# ripples_v90.net
KiCad netlist of a schematic drawn in EAGLE
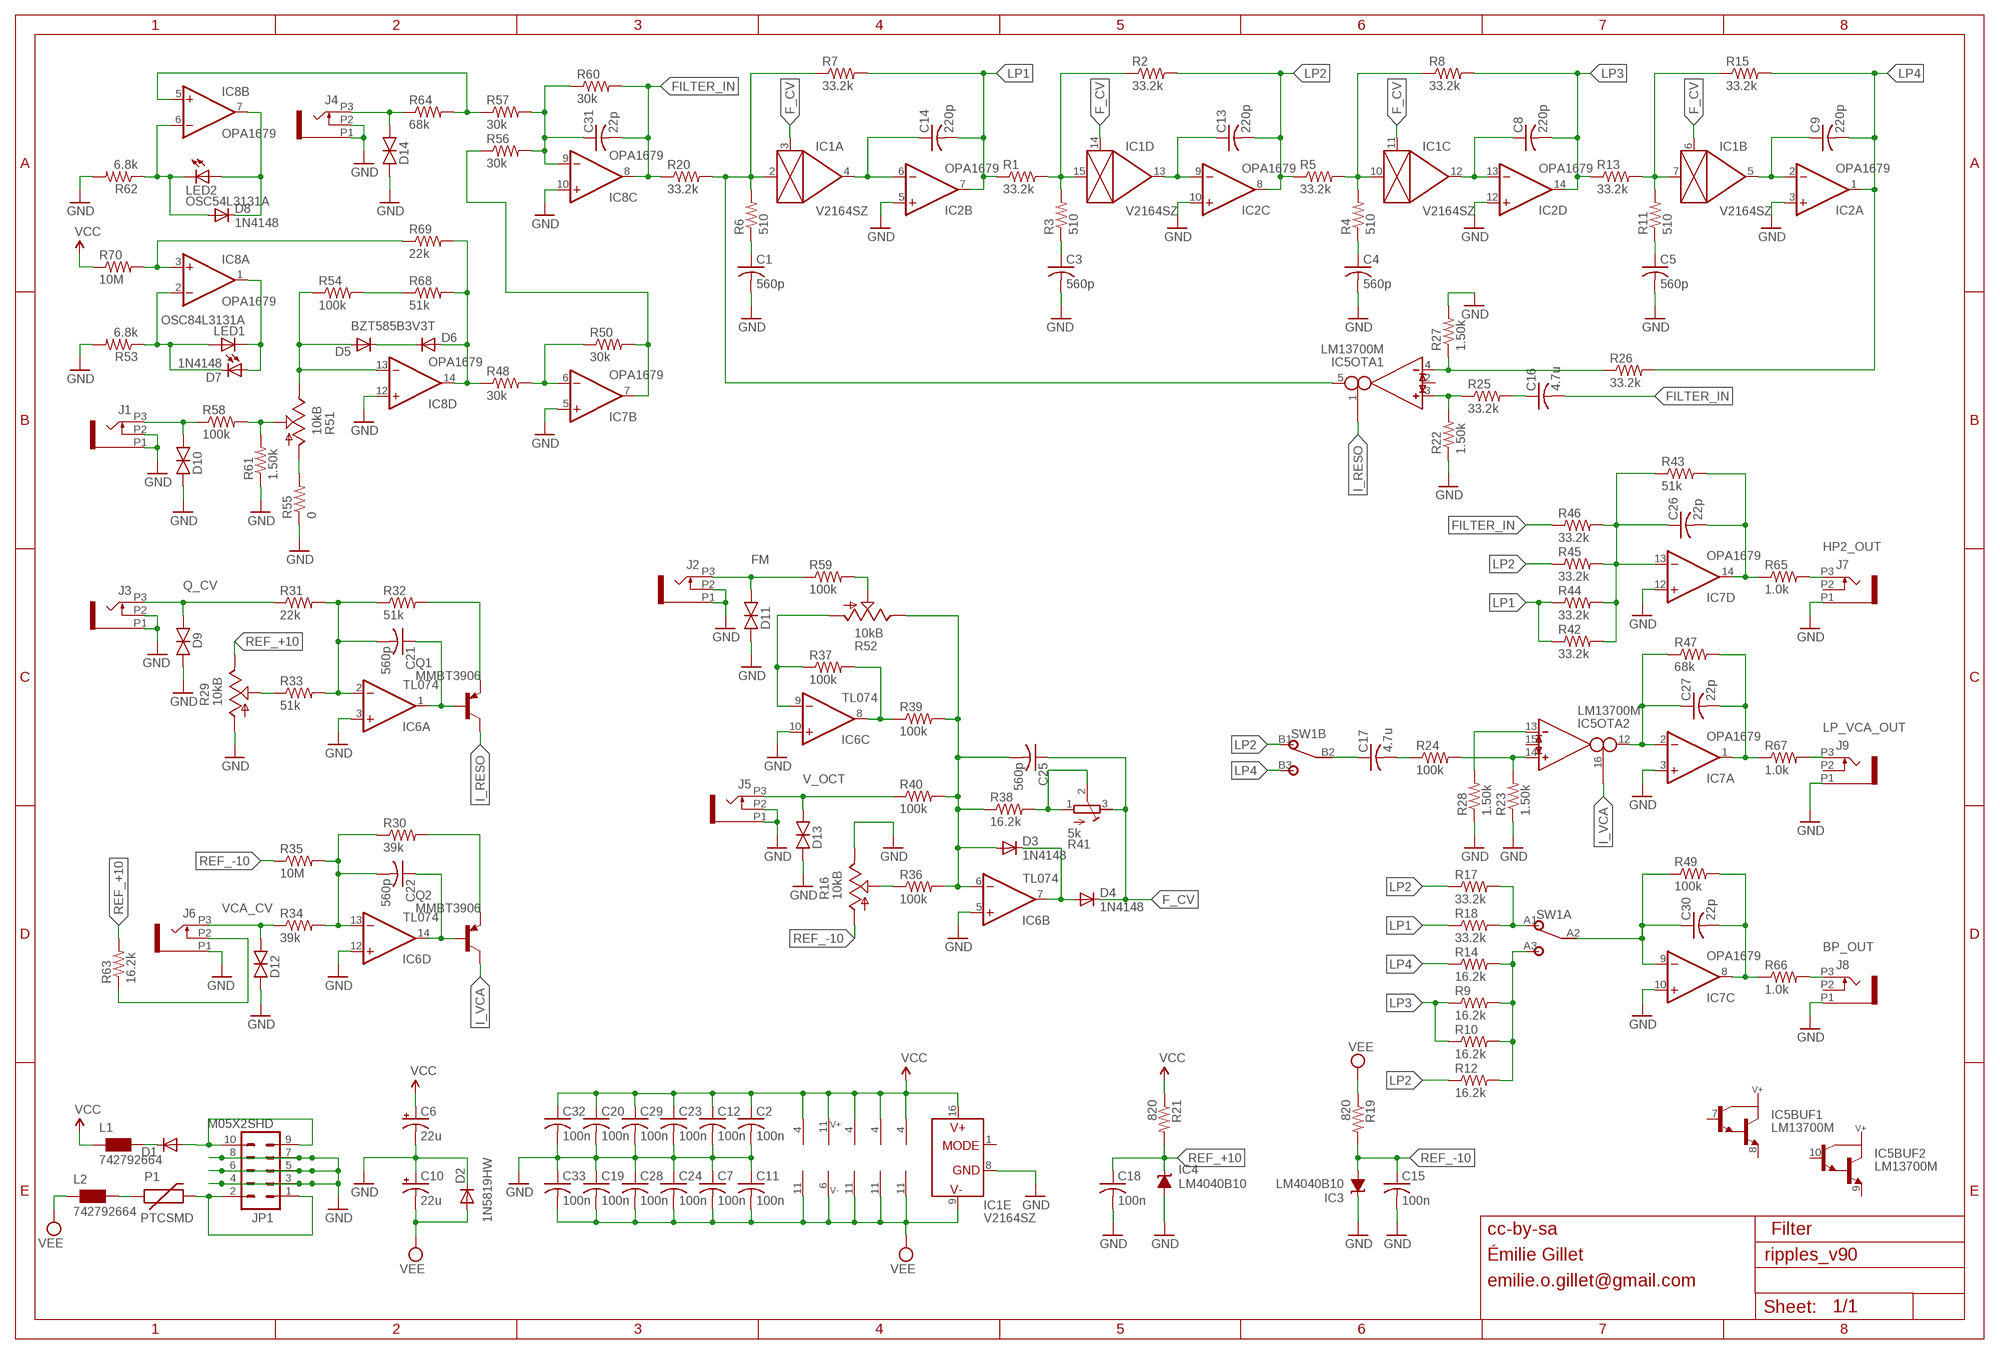
[diagram p0: schematic, sheet 1]

(export (version "E")
  (design (tool "Eeschema 10.0.6"))
  (components
    (comp (ref "C1")
      (value "560p")
      (footprint "eagle-import:C0402")
      (libsource (lib "eagle-import") (part "C-USC0402"))
    )
    (comp (ref "C2")
      (value "100n")
      (footprint "eagle-import:C0402")
      (libsource (lib "eagle-import") (part "C-USC0402"))
    )
    (comp (ref "C3")
      (value "560p")
      (footprint "eagle-import:C0402")
      (libsource (lib "eagle-import") (part "C-USC0402"))
    )
    (comp (ref "C4")
      (value "560p")
      (footprint "eagle-import:C0402")
      (libsource (lib "eagle-import") (part "C-USC0402"))
    )
    (comp (ref "C5")
      (value "560p")
      (footprint "eagle-import:C0402")
      (libsource (lib "eagle-import") (part "C-USC0402"))
    )
    (comp (ref "C6")
      (value "22u")
      (footprint "eagle-import:PANASONIC_B")
      (libsource (lib "eagle-import") (part "CPOL-USB"))
    )
    (comp (ref "C7")
      (value "100n")
      (footprint "eagle-import:C0402")
      (libsource (lib "eagle-import") (part "C-USC0402"))
    )
    (comp (ref "C8")
      (value "220p")
      (footprint "eagle-import:C0603")
      (libsource (lib "eagle-import") (part "C-USC0603"))
    )
    (comp (ref "C9")
      (value "220p")
      (footprint "eagle-import:C0603")
      (libsource (lib "eagle-import") (part "C-USC0603"))
    )
    (comp (ref "C10")
      (value "22u")
      (footprint "eagle-import:PANASONIC_B")
      (libsource (lib "eagle-import") (part "CPOL-USB"))
    )
    (comp (ref "C11")
      (value "100n")
      (footprint "eagle-import:C0402")
      (libsource (lib "eagle-import") (part "C-USC0402"))
    )
    (comp (ref "C12")
      (value "100n")
      (footprint "eagle-import:C0402")
      (libsource (lib "eagle-import") (part "C-USC0402"))
    )
    (comp (ref "C13")
      (value "220p")
      (footprint "eagle-import:C0603")
      (libsource (lib "eagle-import") (part "C-USC0603"))
    )
    (comp (ref "C14")
      (value "220p")
      (footprint "eagle-import:C0603")
      (libsource (lib "eagle-import") (part "C-USC0603"))
    )
    (comp (ref "C15")
      (value "100n")
      (footprint "eagle-import:C0402")
      (libsource (lib "eagle-import") (part "C-USC0402"))
    )
    (comp (ref "C16")
      (value "4.7u")
      (footprint "eagle-import:C1206")
      (libsource (lib "eagle-import") (part "C-USC1206"))
    )
    (comp (ref "C17")
      (value "4.7u")
      (footprint "eagle-import:C1206")
      (libsource (lib "eagle-import") (part "C-USC1206"))
    )
    (comp (ref "C18")
      (value "100n")
      (footprint "eagle-import:C0402")
      (libsource (lib "eagle-import") (part "C-USC0402"))
    )
    (comp (ref "C19")
      (value "100n")
      (footprint "eagle-import:C0402")
      (libsource (lib "eagle-import") (part "C-USC0402"))
    )
    (comp (ref "C20")
      (value "100n")
      (footprint "eagle-import:C0402")
      (libsource (lib "eagle-import") (part "C-USC0402"))
    )
    (comp (ref "C21")
      (value "560p")
      (footprint "eagle-import:C0402")
      (libsource (lib "eagle-import") (part "C-USC0402"))
    )
    (comp (ref "C22")
      (value "560p")
      (footprint "eagle-import:C0402")
      (libsource (lib "eagle-import") (part "C-USC0402"))
    )
    (comp (ref "C23")
      (value "100n")
      (footprint "eagle-import:C0402")
      (libsource (lib "eagle-import") (part "C-USC0402"))
    )
    (comp (ref "C24")
      (value "100n")
      (footprint "eagle-import:C0402")
      (libsource (lib "eagle-import") (part "C-USC0402"))
    )
    (comp (ref "C25")
      (value "560p")
      (footprint "eagle-import:C0402")
      (libsource (lib "eagle-import") (part "C-USC0402"))
    )
    (comp (ref "C26")
      (value "22p")
      (footprint "eagle-import:C0402")
      (libsource (lib "eagle-import") (part "C-USC0402"))
    )
    (comp (ref "C27")
      (value "22p")
      (footprint "eagle-import:C0402")
      (libsource (lib "eagle-import") (part "C-USC0402"))
    )
    (comp (ref "C28")
      (value "100n")
      (footprint "eagle-import:C0402")
      (libsource (lib "eagle-import") (part "C-USC0402"))
    )
    (comp (ref "C29")
      (value "100n")
      (footprint "eagle-import:C0402")
      (libsource (lib "eagle-import") (part "C-USC0402"))
    )
    (comp (ref "C30")
      (value "22p")
      (footprint "eagle-import:C0402")
      (libsource (lib "eagle-import") (part "C-USC0402"))
    )
    (comp (ref "C31")
      (value "22p")
      (footprint "eagle-import:C0402")
      (libsource (lib "eagle-import") (part "C-USC0402"))
    )
    (comp (ref "C32")
      (value "100n")
      (footprint "eagle-import:C0402")
      (libsource (lib "eagle-import") (part "C-USC0402"))
    )
    (comp (ref "C33")
      (value "100n")
      (footprint "eagle-import:C0402")
      (libsource (lib "eagle-import") (part "C-USC0402"))
    )
    (comp (ref "D1")
      (value "1N5819HW")
      (footprint "eagle-import:SOD123")
      (libsource (lib "eagle-import") (part "DIODE-SOD123"))
    )
    (comp (ref "D2")
      (value "1N5819HW")
      (footprint "eagle-import:SOD123")
      (libsource (lib "eagle-import") (part "DIODE-SOD123"))
    )
    (comp (ref "D3")
      (value "1N4148")
      (footprint "eagle-import:SOD523")
      (libsource (lib "eagle-import") (part "DIODE-SOD523"))
    )
    (comp (ref "D4")
      (value "1N4148")
      (footprint "eagle-import:SOD523")
      (libsource (lib "eagle-import") (part "DIODE-SOD523"))
    )
    (comp (ref "D5")
      (value "BZT585B3V3T")
      (footprint "eagle-import:SOD523")
      (libsource (lib "eagle-import") (part "DIODE-SOD523"))
    )
    (comp (ref "D6")
      (value "BZT585B3V3T")
      (footprint "eagle-import:SOD523")
      (libsource (lib "eagle-import") (part "DIODE-SOD523"))
    )
    (comp (ref "D7")
      (value "1N4148")
      (footprint "eagle-import:SOD523")
      (libsource (lib "eagle-import") (part "DIODE-SOD523"))
    )
    (comp (ref "D8")
      (value "1N4148")
      (footprint "eagle-import:SOD523")
      (libsource (lib "eagle-import") (part "DIODE-SOD523"))
    )
    (comp (ref "D9")
      (value "TVS")
      (footprint "eagle-import:0603")
      (libsource (lib "eagle-import") (part "TVS"))
    )
    (comp (ref "D10")
      (value "TVS")
      (footprint "eagle-import:0603")
      (libsource (lib "eagle-import") (part "TVS"))
    )
    (comp (ref "D11")
      (value "TVS")
      (footprint "eagle-import:0603")
      (libsource (lib "eagle-import") (part "TVS"))
    )
    (comp (ref "D12")
      (value "TVS")
      (footprint "eagle-import:0603")
      (libsource (lib "eagle-import") (part "TVS"))
    )
    (comp (ref "D13")
      (value "TVS")
      (footprint "eagle-import:0603")
      (libsource (lib "eagle-import") (part "TVS"))
    )
    (comp (ref "D14")
      (value "TVS")
      (footprint "eagle-import:0603")
      (libsource (lib "eagle-import") (part "TVS"))
    )
    (comp (ref "IC1")
      (value "V2164SZ")
      (footprint "eagle-import:SOIC16N")
      (libsource (lib "eagle-import") (part "SSM2164S"))
    )
    (comp (ref "IC2")
      (value "OPA1679")
      (footprint "eagle-import:TSSOP14_065")
      (libsource (lib "eagle-import") (part "OPA1679PW"))
    )
    (comp (ref "IC3")
      (value "LM4040B10")
      (footprint "eagle-import:DBZ_R-PDSO-G3")
      (libsource (lib "eagle-import") (part "LM4041DBZB12"))
    )
    (comp (ref "IC4")
      (value "LM4040B10")
      (footprint "eagle-import:DBZ_R-PDSO-G3")
      (libsource (lib "eagle-import") (part "LM4041DBZB12"))
    )
    (comp (ref "IC5")
      (value "LM13700M")
      (footprint "eagle-import:SO16")
      (libsource (lib "eagle-import") (part "LM13700M"))
    )
    (comp (ref "IC6")
      (value "TL074")
      (footprint "eagle-import:TSSOP14_065")
      (libsource (lib "eagle-import") (part "TL074PW"))
    )
    (comp (ref "IC7")
      (value "OPA1679")
      (footprint "eagle-import:TSSOP14_065")
      (libsource (lib "eagle-import") (part "OPA1679PW"))
    )
    (comp (ref "IC8")
      (value "OPA1679")
      (footprint "eagle-import:TSSOP14_065")
      (libsource (lib "eagle-import") (part "OPA1679PW"))
    )
    (comp (ref "J1")
      (value "PJ301_THONKICONNTME")
      (footprint "eagle-import:WQP_PJ_301M_TME")
      (libsource (lib "eagle-import") (part "PJ301_THONKICONNTME"))
    )
    (comp (ref "J2")
      (value "PJ301_THONKICONNTME")
      (footprint "eagle-import:WQP_PJ_301M_TME")
      (libsource (lib "eagle-import") (part "PJ301_THONKICONNTME"))
    )
    (comp (ref "J3")
      (value "PJ301_THONKICONNTME")
      (footprint "eagle-import:WQP_PJ_301M_TME")
      (libsource (lib "eagle-import") (part "PJ301_THONKICONNTME"))
    )
    (comp (ref "J4")
      (value "PJ301_THONKICONNTME")
      (footprint "eagle-import:WQP_PJ_301M_TME")
      (libsource (lib "eagle-import") (part "PJ301_THONKICONNTME"))
    )
    (comp (ref "J5")
      (value "PJ301_THONKICONNTME")
      (footprint "eagle-import:WQP_PJ_301M_TME")
      (libsource (lib "eagle-import") (part "PJ301_THONKICONNTME"))
    )
    (comp (ref "J6")
      (value "PJ301_THONKICONNTME")
      (footprint "eagle-import:WQP_PJ_301M_TME")
      (libsource (lib "eagle-import") (part "PJ301_THONKICONNTME"))
    )
    (comp (ref "J7")
      (value "PJ301_THONKICONNTME")
      (footprint "eagle-import:WQP_PJ_301M_TME")
      (libsource (lib "eagle-import") (part "PJ301_THONKICONNTME"))
    )
    (comp (ref "J8")
      (value "PJ301_THONKICONNTME")
      (footprint "eagle-import:WQP_PJ_301M_TME")
      (libsource (lib "eagle-import") (part "PJ301_THONKICONNTME"))
    )
    (comp (ref "J9")
      (value "PJ301_THONKICONNTME")
      (footprint "eagle-import:WQP_PJ_301M_TME")
      (libsource (lib "eagle-import") (part "PJ301_THONKICONNTME"))
    )
    (comp (ref "JP1")
      (value "M05X2SHD")
      (footprint "eagle-import:2X5-SHROUDED")
      (libsource (lib "eagle-import") (part "M05X2SHD"))
    )
    (comp (ref "L1")
      (value "742792664")
      (footprint "eagle-import:0603")
      (libsource (lib "eagle-import") (part "WE-CBF_0603"))
    )
    (comp (ref "L2")
      (value "742792664")
      (footprint "eagle-import:0603")
      (libsource (lib "eagle-import") (part "WE-CBF_0603"))
    )
    (comp (ref "LED1")
      (value "OSC84L3131A")
      (footprint "eagle-import:LED3MM")
      (libsource (lib "eagle-import") (part "LED3MM"))
    )
    (comp (ref "LED2")
      (value "OSC54L3131A")
      (footprint "eagle-import:LED3MM")
      (libsource (lib "eagle-import") (part "LED3MM"))
    )
    (comp (ref "P1")
      (value "PTCSMD")
      (footprint "eagle-import:PTC-1206")
      (libsource (lib "eagle-import") (part "PTCSMD"))
    )
    (comp (ref "Q1")
      (value "MMBT3906")
      (footprint "eagle-import:SOT23-BEC")
      (libsource (lib "eagle-import") (part "-PNP-SOT23-BECMMBT3906LT1"))
    )
    (comp (ref "Q2")
      (value "MMBT3906")
      (footprint "eagle-import:SOT23-BEC")
      (libsource (lib "eagle-import") (part "-PNP-SOT23-BECMMBT3906LT1"))
    )
    (comp (ref "R1")
      (value "33.2k")
      (footprint "eagle-import:R0402")
      (libsource (lib "eagle-import") (part "R-US_R0402"))
    )
    (comp (ref "R2")
      (value "33.2k")
      (footprint "eagle-import:R0402")
      (libsource (lib "eagle-import") (part "R-US_R0402"))
    )
    (comp (ref "R3")
      (value "510")
      (footprint "eagle-import:R0402")
      (libsource (lib "eagle-import") (part "R-US_R0402"))
    )
    (comp (ref "R4")
      (value "510")
      (footprint "eagle-import:R0402")
      (libsource (lib "eagle-import") (part "R-US_R0402"))
    )
    (comp (ref "R5")
      (value "33.2k")
      (footprint "eagle-import:R0402")
      (libsource (lib "eagle-import") (part "R-US_R0402"))
    )
    (comp (ref "R6")
      (value "510")
      (footprint "eagle-import:R0402")
      (libsource (lib "eagle-import") (part "R-US_R0402"))
    )
    (comp (ref "R7")
      (value "33.2k")
      (footprint "eagle-import:R0402")
      (libsource (lib "eagle-import") (part "R-US_R0402"))
    )
    (comp (ref "R8")
      (value "33.2k")
      (footprint "eagle-import:R0402")
      (libsource (lib "eagle-import") (part "R-US_R0402"))
    )
    (comp (ref "R9")
      (value "16.2k")
      (footprint "eagle-import:R0402")
      (libsource (lib "eagle-import") (part "R-US_R0402"))
    )
    (comp (ref "R10")
      (value "16.2k")
      (footprint "eagle-import:R0402")
      (libsource (lib "eagle-import") (part "R-US_R0402"))
    )
    (comp (ref "R11")
      (value "510")
      (footprint "eagle-import:R0402")
      (libsource (lib "eagle-import") (part "R-US_R0402"))
    )
    (comp (ref "R12")
      (value "16.2k")
      (footprint "eagle-import:R0402")
      (libsource (lib "eagle-import") (part "R-US_R0402"))
    )
    (comp (ref "R13")
      (value "33.2k")
      (footprint "eagle-import:R0402")
      (libsource (lib "eagle-import") (part "R-US_R0402"))
    )
    (comp (ref "R14")
      (value "16.2k")
      (footprint "eagle-import:R0402")
      (libsource (lib "eagle-import") (part "R-US_R0402"))
    )
    (comp (ref "R15")
      (value "33.2k")
      (footprint "eagle-import:R0402")
      (libsource (lib "eagle-import") (part "R-US_R0402"))
    )
    (comp (ref "R16")
      (value "10kB")
      (footprint "eagle-import:ALPS_POT_VERTICAL_PS")
      (libsource (lib "eagle-import") (part "POT_USVERTICAL_PS"))
    )
    (comp (ref "R17")
      (value "33.2k")
      (footprint "eagle-import:R0402")
      (libsource (lib "eagle-import") (part "R-US_R0402"))
    )
    (comp (ref "R18")
      (value "33.2k")
      (footprint "eagle-import:R0402")
      (libsource (lib "eagle-import") (part "R-US_R0402"))
    )
    (comp (ref "R19")
      (value "820")
      (footprint "eagle-import:R0402")
      (libsource (lib "eagle-import") (part "resistor_R-US_R0402"))
    )
    (comp (ref "R20")
      (value "33.2k")
      (footprint "eagle-import:R0402")
      (libsource (lib "eagle-import") (part "R-US_R0402"))
    )
    (comp (ref "R21")
      (value "820")
      (footprint "eagle-import:R0402")
      (libsource (lib "eagle-import") (part "R-US_R0402"))
    )
    (comp (ref "R22")
      (value "1.50k")
      (footprint "eagle-import:R0402")
      (libsource (lib "eagle-import") (part "R-US_R0402"))
    )
    (comp (ref "R23")
      (value "1.50k")
      (footprint "eagle-import:R0402")
      (libsource (lib "eagle-import") (part "R-US_R0402"))
    )
    (comp (ref "R24")
      (value "100k")
      (footprint "eagle-import:R0402")
      (libsource (lib "eagle-import") (part "R-US_R0402"))
    )
    (comp (ref "R25")
      (value "33.2k")
      (footprint "eagle-import:R0402")
      (libsource (lib "eagle-import") (part "R-US_R0402"))
    )
    (comp (ref "R26")
      (value "33.2k")
      (footprint "eagle-import:R0402")
      (libsource (lib "eagle-import") (part "R-US_R0402"))
    )
    (comp (ref "R27")
      (value "1.50k")
      (footprint "eagle-import:R0402")
      (libsource (lib "eagle-import") (part "R-US_R0402"))
    )
    (comp (ref "R28")
      (value "1.50k")
      (footprint "eagle-import:R0402")
      (libsource (lib "eagle-import") (part "R-US_R0402"))
    )
    (comp (ref "R29")
      (value "10kB")
      (footprint "eagle-import:ALPS_POT_VERTICAL_PS")
      (libsource (lib "eagle-import") (part "POT_USVERTICAL_PS"))
    )
    (comp (ref "R30")
      (value "39k")
      (footprint "eagle-import:R0402")
      (libsource (lib "eagle-import") (part "R-US_R0402"))
    )
    (comp (ref "R31")
      (value "22k")
      (footprint "eagle-import:R0402")
      (libsource (lib "eagle-import") (part "R-US_R0402"))
    )
    (comp (ref "R32")
      (value "51k")
      (footprint "eagle-import:R0402")
      (libsource (lib "eagle-import") (part "R-US_R0402"))
    )
    (comp (ref "R33")
      (value "51k")
      (footprint "eagle-import:R0402")
      (libsource (lib "eagle-import") (part "R-US_R0402"))
    )
    (comp (ref "R34")
      (value "39k")
      (footprint "eagle-import:R0402")
      (libsource (lib "eagle-import") (part "R-US_R0402"))
    )
    (comp (ref "R35")
      (value "10M")
      (footprint "eagle-import:R0402")
      (libsource (lib "eagle-import") (part "R-US_R0402"))
    )
    (comp (ref "R36")
      (value "100k")
      (footprint "eagle-import:R0402")
      (libsource (lib "eagle-import") (part "R-US_R0402"))
    )
    (comp (ref "R37")
      (value "100k")
      (footprint "eagle-import:R0402")
      (libsource (lib "eagle-import") (part "R-US_R0402"))
    )
    (comp (ref "R38")
      (value "16.2k")
      (footprint "eagle-import:R0402")
      (libsource (lib "eagle-import") (part "R-US_R0402"))
    )
    (comp (ref "R39")
      (value "100k")
      (footprint "eagle-import:R0402")
      (libsource (lib "eagle-import") (part "R-US_R0402"))
    )
    (comp (ref "R40")
      (value "100k")
      (footprint "eagle-import:R0402")
      (libsource (lib "eagle-import") (part "R-US_R0402"))
    )
    (comp (ref "R41")
      (value "5k")
      (footprint "eagle-import:RTRIM3296X")
      (libsource (lib "eagle-import") (part "R-TRIMM3296X"))
    )
    (comp (ref "R42")
      (value "33.2k")
      (footprint "eagle-import:R0402")
      (libsource (lib "eagle-import") (part "R-US_R0402"))
    )
    (comp (ref "R43")
      (value "51k")
      (footprint "eagle-import:R0402")
      (libsource (lib "eagle-import") (part "R-US_R0402"))
    )
    (comp (ref "R44")
      (value "33.2k")
      (footprint "eagle-import:R0402")
      (libsource (lib "eagle-import") (part "R-US_R0402"))
    )
    (comp (ref "R45")
      (value "33.2k")
      (footprint "eagle-import:R0402")
      (libsource (lib "eagle-import") (part "R-US_R0402"))
    )
    (comp (ref "R46")
      (value "33.2k")
      (footprint "eagle-import:R0402")
      (libsource (lib "eagle-import") (part "R-US_R0402"))
    )
    (comp (ref "R47")
      (value "68k")
      (footprint "eagle-import:R0402")
      (libsource (lib "eagle-import") (part "R-US_R0402"))
    )
    (comp (ref "R48")
      (value "30k")
      (footprint "eagle-import:R0402")
      (libsource (lib "eagle-import") (part "R-US_R0402"))
    )
    (comp (ref "R49")
      (value "100k")
      (footprint "eagle-import:R0402")
      (libsource (lib "eagle-import") (part "R-US_R0402"))
    )
    (comp (ref "R50")
      (value "30k")
      (footprint "eagle-import:R0402")
      (libsource (lib "eagle-import") (part "R-US_R0402"))
    )
    (comp (ref "R51")
      (value "10kB")
      (footprint "eagle-import:ALPS_POT_NARROW")
      (libsource (lib "eagle-import") (part "POT_USVERTICAL_NARROW"))
    )
    (comp (ref "R52")
      (value "10kB")
      (footprint "eagle-import:ALPS_POT_NARROW")
      (libsource (lib "eagle-import") (part "POT_USVERTICAL_NARROW"))
    )
    (comp (ref "R53")
      (value "6.8k")
      (footprint "eagle-import:R0402")
      (libsource (lib "eagle-import") (part "R-US_R0402"))
    )
    (comp (ref "R54")
      (value "100k")
      (footprint "eagle-import:R0402")
      (libsource (lib "eagle-import") (part "R-US_R0402"))
    )
    (comp (ref "R55")
      (value "0")
      (footprint "eagle-import:R0402")
      (libsource (lib "eagle-import") (part "R-US_R0402"))
    )
    (comp (ref "R56")
      (value "30k")
      (footprint "eagle-import:R0402")
      (libsource (lib "eagle-import") (part "R-US_R0402"))
    )
    (comp (ref "R57")
      (value "30k")
      (footprint "eagle-import:R0402")
      (libsource (lib "eagle-import") (part "R-US_R0402"))
    )
    (comp (ref "R58")
      (value "100k")
      (footprint "eagle-import:R0402")
      (libsource (lib "eagle-import") (part "R-US_R0402"))
    )
    (comp (ref "R59")
      (value "100k")
      (footprint "eagle-import:R0402")
      (libsource (lib "eagle-import") (part "R-US_R0402"))
    )
    (comp (ref "R60")
      (value "30k")
      (footprint "eagle-import:R0402")
      (libsource (lib "eagle-import") (part "R-US_R0402"))
    )
    (comp (ref "R61")
      (value "1.50k")
      (footprint "eagle-import:R0402")
      (libsource (lib "eagle-import") (part "R-US_R0402"))
    )
    (comp (ref "R62")
      (value "6.8k")
      (footprint "eagle-import:R0402")
      (libsource (lib "eagle-import") (part "R-US_R0402"))
    )
    (comp (ref "R63")
      (value "16.2k")
      (footprint "eagle-import:R0402")
      (libsource (lib "eagle-import") (part "R-US_R0402"))
    )
    (comp (ref "R64")
      (value "68k")
      (footprint "eagle-import:R0402")
      (libsource (lib "eagle-import") (part "R-US_R0402"))
    )
    (comp (ref "R65")
      (value "1.0k")
      (footprint "eagle-import:R0603")
      (libsource (lib "eagle-import") (part "R-US_R0603"))
    )
    (comp (ref "R66")
      (value "1.0k")
      (footprint "eagle-import:R0603")
      (libsource (lib "eagle-import") (part "R-US_R0603"))
    )
    (comp (ref "R67")
      (value "1.0k")
      (footprint "eagle-import:R0603")
      (libsource (lib "eagle-import") (part "R-US_R0603"))
    )
    (comp (ref "R68")
      (value "51k")
      (footprint "eagle-import:R0402")
      (libsource (lib "eagle-import") (part "R-US_R0402"))
    )
    (comp (ref "R69")
      (value "22k")
      (footprint "eagle-import:R0402")
      (libsource (lib "eagle-import") (part "R-US_R0402"))
    )
    (comp (ref "R70")
      (value "10M")
      (footprint "eagle-import:R0402")
      (libsource (lib "eagle-import") (part "R-US_R0402"))
    )
    (comp (ref "SW1")
      (value "S-ON-ON-ONSS70070F-0202")
      (footprint "eagle-import:SS70070F-0202")
      (libsource (lib "eagle-import") (part "S-ON-ON-ONSS70070F-0202"))
    )
  )
  (nets
    (net (code "1") (name "/BP_OUT") (class "Default")
      (node (ref "J8") (pin "P3") (pinfunction "3_P3") (pintype "passive"))
      (node (ref "R66") (pin "2") (pinfunction "2_2") (pintype "passive"))
    )
    (net (code "2") (name "/FM") (class "Default")
      (node (ref "D11") (pin "2") (pinfunction "C_2") (pintype "passive"))
      (node (ref "J2") (pin "P3") (pinfunction "3_P3") (pintype "passive"))
      (node (ref "R59") (pin "1") (pinfunction "1_1") (pintype "passive"))
    )
    (net (code "3") (name "/HP2_OUT") (class "Default")
      (node (ref "J7") (pin "P3") (pinfunction "3_P3") (pintype "passive"))
      (node (ref "R65") (pin "2") (pinfunction "2_2") (pintype "passive"))
    )
    (net (code "4") (name "/LP_VCA_OUT") (class "Default")
      (node (ref "J9") (pin "P3") (pinfunction "3_P3") (pintype "passive"))
      (node (ref "R67") (pin "2") (pinfunction "2_2") (pintype "passive"))
    )
    (net (code "5") (name "/Q_CV") (class "Default")
      (node (ref "D9") (pin "2") (pinfunction "C_2") (pintype "passive"))
      (node (ref "J3") (pin "P3") (pinfunction "3_P3") (pintype "passive"))
      (node (ref "R31") (pin "1") (pinfunction "1_1") (pintype "passive"))
    )
    (net (code "6") (name "/VCA_CV") (class "Default")
      (node (ref "D12") (pin "2") (pinfunction "C_2") (pintype "passive"))
      (node (ref "J6") (pin "P3") (pinfunction "3_P3") (pintype "passive"))
      (node (ref "R34") (pin "1") (pinfunction "1_1") (pintype "passive"))
    )
    (net (code "7") (name "/V_OCT") (class "Default")
      (node (ref "D13") (pin "2") (pinfunction "C_2") (pintype "passive"))
      (node (ref "J5") (pin "P3") (pinfunction "3_P3") (pintype "passive"))
      (node (ref "R40") (pin "1") (pinfunction "1_1") (pintype "passive"))
    )
    (net (code "8") (name "FILTER_IN") (class "Default")
      (node (ref "C16") (pin "2") (pinfunction "2_2") (pintype "passive"))
      (node (ref "C31") (pin "2") (pinfunction "2_2") (pintype "passive"))
      (node (ref "IC8") (pin "8") (pinfunction "OUT_8") (pintype "output"))
      (node (ref "R20") (pin "1") (pinfunction "1_1") (pintype "passive"))
      (node (ref "R46") (pin "1") (pinfunction "1_1") (pintype "passive"))
      (node (ref "R60") (pin "2") (pinfunction "2_2") (pintype "passive"))
    )
    (net (code "9") (name "F_CV") (class "Default")
      (node (ref "C25") (pin "1") (pinfunction "1_1") (pintype "passive"))
      (node (ref "D4") (pin "C") (pinfunction "C_C") (pintype "passive"))
      (node (ref "IC1") (pin "11") (pinfunction "CTRL_11") (pintype "input"))
      (node (ref "IC1") (pin "14") (pinfunction "CTRL_14") (pintype "input"))
      (node (ref "IC1") (pin "3") (pinfunction "CTRL_3") (pintype "input"))
      (node (ref "IC1") (pin "6") (pinfunction "CTRL_6") (pintype "input"))
      (node (ref "R41") (pin "3") (pinfunction "A_3") (pintype "passive"))
    )
    (net (code "10") (name "GND") (class "Default")
      (node (ref "C1") (pin "2") (pinfunction "2_2") (pintype "passive"))
      (node (ref "C10") (pin "+") (pinfunction "+_+") (pintype "passive"))
      (node (ref "C11") (pin "1") (pinfunction "1_1") (pintype "passive"))
      (node (ref "C12") (pin "2") (pinfunction "2_2") (pintype "passive"))
      (node (ref "C15") (pin "2") (pinfunction "2_2") (pintype "passive"))
      (node (ref "C18") (pin "2") (pinfunction "2_2") (pintype "passive"))
      (node (ref "C19") (pin "1") (pinfunction "1_1") (pintype "passive"))
      (node (ref "C2") (pin "2") (pinfunction "2_2") (pintype "passive"))
      (node (ref "C20") (pin "2") (pinfunction "2_2") (pintype "passive"))
      (node (ref "C23") (pin "2") (pinfunction "2_2") (pintype "passive"))
      (node (ref "C24") (pin "1") (pinfunction "1_1") (pintype "passive"))
      (node (ref "C28") (pin "1") (pinfunction "1_1") (pintype "passive"))
      (node (ref "C29") (pin "2") (pinfunction "2_2") (pintype "passive"))
      (node (ref "C3") (pin "2") (pinfunction "2_2") (pintype "passive"))
      (node (ref "C32") (pin "2") (pinfunction "2_2") (pintype "passive"))
      (node (ref "C33") (pin "1") (pinfunction "1_1") (pintype "passive"))
      (node (ref "C4") (pin "2") (pinfunction "2_2") (pintype "passive"))
      (node (ref "C5") (pin "2") (pinfunction "2_2") (pintype "passive"))
      (node (ref "C6") (pin "-") (pinfunction "-_-") (pintype "passive"))
      (node (ref "C7") (pin "1") (pinfunction "1_1") (pintype "passive"))
      (node (ref "D10") (pin "1") (pinfunction "A_1") (pintype "passive"))
      (node (ref "D11") (pin "1") (pinfunction "A_1") (pintype "passive"))
      (node (ref "D12") (pin "1") (pinfunction "A_1") (pintype "passive"))
      (node (ref "D13") (pin "1") (pinfunction "A_1") (pintype "passive"))
      (node (ref "D14") (pin "1") (pinfunction "A_1") (pintype "passive"))
      (node (ref "D2") (pin "C") (pinfunction "C_C") (pintype "passive"))
      (node (ref "D9") (pin "1") (pinfunction "A_1") (pintype "passive"))
      (node (ref "IC1") (pin "8") (pinfunction "GND_8") (pintype "power_in"))
      (node (ref "IC2") (pin "10") (pinfunction "+IN_10") (pintype "input"))
      (node (ref "IC2") (pin "12") (pinfunction "+IN_12") (pintype "input"))
      (node (ref "IC2") (pin "3") (pinfunction "+IN_3") (pintype "input"))
      (node (ref "IC2") (pin "5") (pinfunction "+IN_5") (pintype "input"))
      (node (ref "IC3") (pin "1") (pinfunction "C_1") (pintype "passive"))
      (node (ref "IC4") (pin "2") (pinfunction "A_2") (pintype "passive"))
      (node (ref "IC6") (pin "10") (pinfunction "+IN_10") (pintype "input"))
      (node (ref "IC6") (pin "12") (pinfunction "+IN_12") (pintype "input"))
      (node (ref "IC6") (pin "3") (pinfunction "+IN_3") (pintype "input"))
      (node (ref "IC6") (pin "5") (pinfunction "+IN_5") (pintype "input"))
      (node (ref "IC7") (pin "10") (pinfunction "+IN_10") (pintype "input"))
      (node (ref "IC7") (pin "12") (pinfunction "+IN_12") (pintype "input"))
      (node (ref "IC7") (pin "3") (pinfunction "+IN_3") (pintype "input"))
      (node (ref "IC7") (pin "5") (pinfunction "+IN_5") (pintype "input"))
      (node (ref "IC8") (pin "10") (pinfunction "+IN_10") (pintype "input"))
      (node (ref "IC8") (pin "12") (pinfunction "+IN_12") (pintype "input"))
      (node (ref "J1") (pin "P1") (pinfunction "1_P1") (pintype "passive"))
      (node (ref "J1") (pin "P2") (pinfunction "2_P2") (pintype "passive"))
      (node (ref "J2") (pin "P1") (pinfunction "1_P1") (pintype "passive"))
      (node (ref "J2") (pin "P2") (pinfunction "2_P2") (pintype "passive"))
      (node (ref "J3") (pin "P1") (pinfunction "1_P1") (pintype "passive"))
      (node (ref "J3") (pin "P2") (pinfunction "2_P2") (pintype "passive"))
      (node (ref "J4") (pin "P1") (pinfunction "1_P1") (pintype "passive"))
      (node (ref "J4") (pin "P2") (pinfunction "2_P2") (pintype "passive"))
      (node (ref "J5") (pin "P1") (pinfunction "1_P1") (pintype "passive"))
      (node (ref "J5") (pin "P2") (pinfunction "2_P2") (pintype "passive"))
      (node (ref "J6") (pin "P1") (pinfunction "1_P1") (pintype "passive"))
      (node (ref "J7") (pin "P1") (pinfunction "1_P1") (pintype "passive"))
      (node (ref "J8") (pin "P1") (pinfunction "1_P1") (pintype "passive"))
      (node (ref "J9") (pin "P1") (pinfunction "1_P1") (pintype "passive"))
      (node (ref "JP1") (pin "3") (pinfunction "3_3") (pintype "passive"))
      (node (ref "JP1") (pin "4") (pinfunction "4_4") (pintype "passive"))
      (node (ref "JP1") (pin "5") (pinfunction "5_5") (pintype "passive"))
      (node (ref "JP1") (pin "6") (pinfunction "6_6") (pintype "passive"))
      (node (ref "JP1") (pin "7") (pinfunction "7_7") (pintype "passive"))
      (node (ref "JP1") (pin "8") (pinfunction "8_8") (pintype "passive"))
      (node (ref "R16") (pin "P$1") (pinfunction "E_P$1") (pintype "passive"))
      (node (ref "R22") (pin "1") (pinfunction "1_1") (pintype "passive"))
      (node (ref "R23") (pin "1") (pinfunction "1_1") (pintype "passive"))
      (node (ref "R27") (pin "2") (pinfunction "2_2") (pintype "passive"))
      (node (ref "R28") (pin "1") (pinfunction "1_1") (pintype "passive"))
      (node (ref "R29") (pin "P$3") (pinfunction "A_P$3") (pintype "passive"))
      (node (ref "R53") (pin "2") (pinfunction "2_2") (pintype "passive"))
      (node (ref "R55") (pin "1") (pinfunction "1_1") (pintype "passive"))
      (node (ref "R61") (pin "1") (pinfunction "1_1") (pintype "passive"))
      (node (ref "R62") (pin "2") (pinfunction "2_2") (pintype "passive"))
    )
    (net (code "11") (name "I_RESO") (class "Default")
      (node (ref "IC5") (pin "1") (pinfunction "I_BIAS_1") (pintype "input"))
      (node (ref "Q1") (pin "C") (pinfunction "C_C") (pintype "passive"))
    )
    (net (code "12") (name "I_VCA") (class "Default")
      (node (ref "IC5") (pin "16") (pinfunction "I_BIAS_16") (pintype "input"))
      (node (ref "Q2") (pin "C") (pinfunction "C_C") (pintype "passive"))
    )
    (net (code "13") (name "LP1") (class "Default")
      (node (ref "C14") (pin "2") (pinfunction "2_2") (pintype "passive"))
      (node (ref "IC2") (pin "7") (pinfunction "OUT_7") (pintype "output"))
      (node (ref "R1") (pin "1") (pinfunction "1_1") (pintype "passive"))
      (node (ref "R18") (pin "1") (pinfunction "1_1") (pintype "passive"))
      (node (ref "R42") (pin "1") (pinfunction "1_1") (pintype "passive"))
      (node (ref "R44") (pin "1") (pinfunction "1_1") (pintype "passive"))
      (node (ref "R7") (pin "2") (pinfunction "2_2") (pintype "passive"))
    )
    (net (code "14") (name "LP2") (class "Default")
      (node (ref "C13") (pin "2") (pinfunction "2_2") (pintype "passive"))
      (node (ref "IC2") (pin "8") (pinfunction "OUT_8") (pintype "output"))
      (node (ref "R12") (pin "1") (pinfunction "1_1") (pintype "passive"))
      (node (ref "R17") (pin "1") (pinfunction "1_1") (pintype "passive"))
      (node (ref "R2") (pin "2") (pinfunction "2_2") (pintype "passive"))
      (node (ref "R45") (pin "1") (pinfunction "1_1") (pintype "passive"))
      (node (ref "R5") (pin "1") (pinfunction "1_1") (pintype "passive"))
      (node (ref "SW1") (pin "B1") (pinfunction "1_B1") (pintype "passive"))
    )
    (net (code "15") (name "LP3") (class "Default")
      (node (ref "C8") (pin "2") (pinfunction "2_2") (pintype "passive"))
      (node (ref "IC2") (pin "14") (pinfunction "OUT_14") (pintype "output"))
      (node (ref "R10") (pin "1") (pinfunction "1_1") (pintype "passive"))
      (node (ref "R13") (pin "1") (pinfunction "1_1") (pintype "passive"))
      (node (ref "R8") (pin "2") (pinfunction "2_2") (pintype "passive"))
      (node (ref "R9") (pin "1") (pinfunction "1_1") (pintype "passive"))
    )
    (net (code "16") (name "LP4") (class "Default")
      (node (ref "C9") (pin "2") (pinfunction "2_2") (pintype "passive"))
      (node (ref "IC2") (pin "1") (pinfunction "OUT_1") (pintype "output"))
      (node (ref "R14") (pin "1") (pinfunction "1_1") (pintype "passive"))
      (node (ref "R15") (pin "2") (pinfunction "2_2") (pintype "passive"))
      (node (ref "R26") (pin "2") (pinfunction "2_2") (pintype "passive"))
      (node (ref "SW1") (pin "B3") (pinfunction "3_B3") (pintype "passive"))
    )
    (net (code "17") (name "Net-(C1-Pad1)") (class "Default")
      (node (ref "C1") (pin "1") (pinfunction "1_1") (pintype "passive"))
      (node (ref "R6") (pin "1") (pinfunction "1_1") (pintype "passive"))
    )
    (net (code "18") (name "Net-(C3-Pad1)") (class "Default")
      (node (ref "C3") (pin "1") (pinfunction "1_1") (pintype "passive"))
      (node (ref "R3") (pin "1") (pinfunction "1_1") (pintype "passive"))
    )
    (net (code "19") (name "Net-(C4-Pad1)") (class "Default")
      (node (ref "C4") (pin "1") (pinfunction "1_1") (pintype "passive"))
      (node (ref "R4") (pin "1") (pinfunction "1_1") (pintype "passive"))
    )
    (net (code "20") (name "Net-(C5-Pad1)") (class "Default")
      (node (ref "C5") (pin "1") (pinfunction "1_1") (pintype "passive"))
      (node (ref "R11") (pin "1") (pinfunction "1_1") (pintype "passive"))
    )
    (net (code "21") (name "Net-(C16-Pad1)") (class "Default")
      (node (ref "C16") (pin "1") (pinfunction "1_1") (pintype "passive"))
      (node (ref "R25") (pin "2") (pinfunction "2_2") (pintype "passive"))
    )
    (net (code "22") (name "Net-(C17-Pad2)") (class "Default")
      (node (ref "C17") (pin "2") (pinfunction "2_2") (pintype "passive"))
      (node (ref "R24") (pin "1") (pinfunction "1_1") (pintype "passive"))
    )
    (net (code "23") (name "Net-(D1-PadA)") (class "Default")
      (node (ref "D1") (pin "A") (pinfunction "A_A") (pintype "passive"))
      (node (ref "JP1") (pin "10") (pinfunction "10_10") (pintype "passive"))
      (node (ref "JP1") (pin "9") (pinfunction "9_9") (pintype "passive"))
    )
    (net (code "24") (name "Net-(D1-PadC)") (class "Default")
      (node (ref "D1") (pin "C") (pinfunction "C_C") (pintype "passive"))
      (node (ref "L1") (pin "2") (pinfunction "2_2") (pintype "passive"))
    )
    (net (code "25") (name "Net-(D5-PadC)") (class "Default")
      (node (ref "D5") (pin "C") (pinfunction "C_C") (pintype "passive"))
      (node (ref "D6") (pin "C") (pinfunction "C_C") (pintype "passive"))
    )
    (net (code "26") (name "Net-(D10-C)") (class "Default")
      (node (ref "D10") (pin "2") (pinfunction "C_2") (pintype "passive"))
      (node (ref "J1") (pin "P3") (pinfunction "3_P3") (pintype "passive"))
      (node (ref "R58") (pin "1") (pinfunction "1_1") (pintype "passive"))
    )
    (net (code "27") (name "Net-(D14-C)") (class "Default")
      (node (ref "D14") (pin "2") (pinfunction "C_2") (pintype "passive"))
      (node (ref "J4") (pin "P3") (pinfunction "3_P3") (pintype "passive"))
      (node (ref "R64") (pin "1") (pinfunction "1_1") (pintype "passive"))
    )
    (net (code "28") (name "Net-(IC1A-IN)") (class "Default")
      (node (ref "IC1") (pin "2") (pinfunction "IN_2") (pintype "input"))
      (node (ref "IC5") (pin "5") (pinfunction "OUT_5") (pintype "output"))
      (node (ref "R20") (pin "2") (pinfunction "2_2") (pintype "passive"))
      (node (ref "R6") (pin "2") (pinfunction "2_2") (pintype "passive"))
      (node (ref "R7") (pin "1") (pinfunction "1_1") (pintype "passive"))
    )
    (net (code "29") (name "Net-(IC1A-OUT)") (class "Default")
      (node (ref "C14") (pin "1") (pinfunction "1_1") (pintype "passive"))
      (node (ref "IC1") (pin "4") (pinfunction "OUT_4") (pintype "output"))
      (node (ref "IC2") (pin "6") (pinfunction "-IN_6") (pintype "input"))
    )
    (net (code "30") (name "Net-(IC1B-IN)") (class "Default")
      (node (ref "IC1") (pin "7") (pinfunction "IN_7") (pintype "input"))
      (node (ref "R11") (pin "2") (pinfunction "2_2") (pintype "passive"))
      (node (ref "R13") (pin "2") (pinfunction "2_2") (pintype "passive"))
      (node (ref "R15") (pin "1") (pinfunction "1_1") (pintype "passive"))
    )
    (net (code "31") (name "Net-(IC1B-OUT)") (class "Default")
      (node (ref "C9") (pin "1") (pinfunction "1_1") (pintype "passive"))
      (node (ref "IC1") (pin "5") (pinfunction "OUT_5") (pintype "output"))
      (node (ref "IC2") (pin "2") (pinfunction "-IN_2") (pintype "input"))
    )
    (net (code "32") (name "Net-(IC1C-IN)") (class "Default")
      (node (ref "IC1") (pin "10") (pinfunction "IN_10") (pintype "input"))
      (node (ref "R4") (pin "2") (pinfunction "2_2") (pintype "passive"))
      (node (ref "R5") (pin "2") (pinfunction "2_2") (pintype "passive"))
      (node (ref "R8") (pin "1") (pinfunction "1_1") (pintype "passive"))
    )
    (net (code "33") (name "Net-(IC1C-OUT)") (class "Default")
      (node (ref "C8") (pin "1") (pinfunction "1_1") (pintype "passive"))
      (node (ref "IC1") (pin "12") (pinfunction "OUT_12") (pintype "output"))
      (node (ref "IC2") (pin "13") (pinfunction "-IN_13") (pintype "input"))
    )
    (net (code "34") (name "Net-(IC1D-IN)") (class "Default")
      (node (ref "IC1") (pin "15") (pinfunction "IN_15") (pintype "input"))
      (node (ref "R1") (pin "2") (pinfunction "2_2") (pintype "passive"))
      (node (ref "R2") (pin "1") (pinfunction "1_1") (pintype "passive"))
      (node (ref "R3") (pin "2") (pinfunction "2_2") (pintype "passive"))
    )
    (net (code "35") (name "Net-(IC1D-OUT)") (class "Default")
      (node (ref "C13") (pin "1") (pinfunction "1_1") (pintype "passive"))
      (node (ref "IC1") (pin "13") (pinfunction "OUT_13") (pintype "output"))
      (node (ref "IC2") (pin "9") (pinfunction "-IN_9") (pintype "input"))
    )
    (net (code "36") (name "Net-(IC5C-IN_N)") (class "Default")
      (node (ref "IC5") (pin "4") (pinfunction "IN_N_4") (pintype "input"))
      (node (ref "R26") (pin "1") (pinfunction "1_1") (pintype "passive"))
      (node (ref "R27") (pin "1") (pinfunction "1_1") (pintype "passive"))
    )
    (net (code "37") (name "Net-(IC5C-IN_P)") (class "Default")
      (node (ref "IC5") (pin "3") (pinfunction "IN_P_3") (pintype "input"))
      (node (ref "R22") (pin "2") (pinfunction "2_2") (pintype "passive"))
      (node (ref "R25") (pin "1") (pinfunction "1_1") (pintype "passive"))
    )
    (net (code "38") (name "Net-(IC5D-IN_N)") (class "Default")
      (node (ref "IC5") (pin "13") (pinfunction "IN_N_13") (pintype "input"))
      (node (ref "R28") (pin "2") (pinfunction "2_2") (pintype "passive"))
    )
    (net (code "39") (name "Net-(IC5D-IN_P)") (class "Default")
      (node (ref "IC5") (pin "14") (pinfunction "IN_P_14") (pintype "input"))
      (node (ref "R23") (pin "2") (pinfunction "2_2") (pintype "passive"))
      (node (ref "R24") (pin "2") (pinfunction "2_2") (pintype "passive"))
    )
    (net (code "40") (name "Net-(IC5D-OUT)") (class "Default")
      (node (ref "C27") (pin "1") (pinfunction "1_1") (pintype "passive"))
      (node (ref "IC5") (pin "12") (pinfunction "OUT_12") (pintype "output"))
      (node (ref "IC7") (pin "2") (pinfunction "-IN_2") (pintype "input"))
      (node (ref "R47") (pin "1") (pinfunction "1_1") (pintype "passive"))
    )
    (net (code "41") (name "Net-(IC6A--IN)") (class "Default")
      (node (ref "C21") (pin "2") (pinfunction "2_2") (pintype "passive"))
      (node (ref "IC6") (pin "2") (pinfunction "-IN_2") (pintype "input"))
      (node (ref "R31") (pin "2") (pinfunction "2_2") (pintype "passive"))
      (node (ref "R32") (pin "1") (pinfunction "1_1") (pintype "passive"))
      (node (ref "R33") (pin "2") (pinfunction "2_2") (pintype "passive"))
    )
    (net (code "42") (name "Net-(IC6A-OUT)") (class "Default")
      (node (ref "C21") (pin "1") (pinfunction "1_1") (pintype "passive"))
      (node (ref "IC6") (pin "1") (pinfunction "OUT_1") (pintype "output"))
      (node (ref "Q1") (pin "B") (pinfunction "B_B") (pintype "passive"))
    )
    (net (code "43") (name "Net-(IC6B--IN)") (class "Default")
      (node (ref "C25") (pin "2") (pinfunction "2_2") (pintype "passive"))
      (node (ref "D3") (pin "A") (pinfunction "A_A") (pintype "passive"))
      (node (ref "IC6") (pin "6") (pinfunction "-IN_6") (pintype "input"))
      (node (ref "R36") (pin "2") (pinfunction "2_2") (pintype "passive"))
      (node (ref "R38") (pin "1") (pinfunction "1_1") (pintype "passive"))
      (node (ref "R39") (pin "2") (pinfunction "2_2") (pintype "passive"))
      (node (ref "R40") (pin "2") (pinfunction "2_2") (pintype "passive"))
      (node (ref "R52") (pin "P$1") (pinfunction "E_P$1") (pintype "passive"))
    )
    (net (code "44") (name "Net-(IC6B-OUT)") (class "Default")
      (node (ref "D3") (pin "C") (pinfunction "C_C") (pintype "passive"))
      (node (ref "D4") (pin "A") (pinfunction "A_A") (pintype "passive"))
      (node (ref "IC6") (pin "7") (pinfunction "OUT_7") (pintype "output"))
    )
    (net (code "45") (name "Net-(IC6C--IN)") (class "Default")
      (node (ref "IC6") (pin "9") (pinfunction "-IN_9") (pintype "input"))
      (node (ref "R37") (pin "1") (pinfunction "1_1") (pintype "passive"))
      (node (ref "R52") (pin "P$3") (pinfunction "A_P$3") (pintype "passive"))
    )
    (net (code "46") (name "Net-(IC6C-OUT)") (class "Default")
      (node (ref "IC6") (pin "8") (pinfunction "OUT_8") (pintype "output"))
      (node (ref "R37") (pin "2") (pinfunction "2_2") (pintype "passive"))
      (node (ref "R39") (pin "1") (pinfunction "1_1") (pintype "passive"))
    )
    (net (code "47") (name "Net-(IC6D--IN)") (class "Default")
      (node (ref "C22") (pin "2") (pinfunction "2_2") (pintype "passive"))
      (node (ref "IC6") (pin "13") (pinfunction "-IN_13") (pintype "input"))
      (node (ref "R30") (pin "1") (pinfunction "1_1") (pintype "passive"))
      (node (ref "R34") (pin "2") (pinfunction "2_2") (pintype "passive"))
      (node (ref "R35") (pin "2") (pinfunction "2_2") (pintype "passive"))
    )
    (net (code "48") (name "Net-(IC6D-OUT)") (class "Default")
      (node (ref "C22") (pin "1") (pinfunction "1_1") (pintype "passive"))
      (node (ref "IC6") (pin "14") (pinfunction "OUT_14") (pintype "output"))
      (node (ref "Q2") (pin "B") (pinfunction "B_B") (pintype "passive"))
    )
    (net (code "49") (name "Net-(IC7A-OUT)") (class "Default")
      (node (ref "C27") (pin "2") (pinfunction "2_2") (pintype "passive"))
      (node (ref "IC7") (pin "1") (pinfunction "OUT_1") (pintype "output"))
      (node (ref "R47") (pin "2") (pinfunction "2_2") (pintype "passive"))
      (node (ref "R67") (pin "1") (pinfunction "1_1") (pintype "passive"))
    )
    (net (code "50") (name "Net-(IC7B--IN)") (class "Default")
      (node (ref "IC7") (pin "6") (pinfunction "-IN_6") (pintype "input"))
      (node (ref "R48") (pin "2") (pinfunction "2_2") (pintype "passive"))
      (node (ref "R50") (pin "1") (pinfunction "1_1") (pintype "passive"))
    )
    (net (code "51") (name "Net-(IC7B-OUT)") (class "Default")
      (node (ref "IC7") (pin "7") (pinfunction "OUT_7") (pintype "output"))
      (node (ref "R50") (pin "2") (pinfunction "2_2") (pintype "passive"))
      (node (ref "R56") (pin "1") (pinfunction "1_1") (pintype "passive"))
    )
    (net (code "52") (name "Net-(IC7C--IN)") (class "Default")
      (node (ref "C30") (pin "1") (pinfunction "1_1") (pintype "passive"))
      (node (ref "IC7") (pin "9") (pinfunction "-IN_9") (pintype "input"))
      (node (ref "R49") (pin "1") (pinfunction "1_1") (pintype "passive"))
      (node (ref "SW1") (pin "A2") (pinfunction "2_A2") (pintype "passive"))
    )
    (net (code "53") (name "Net-(IC7C-OUT)") (class "Default")
      (node (ref "C30") (pin "2") (pinfunction "2_2") (pintype "passive"))
      (node (ref "IC7") (pin "8") (pinfunction "OUT_8") (pintype "output"))
      (node (ref "R49") (pin "2") (pinfunction "2_2") (pintype "passive"))
      (node (ref "R66") (pin "1") (pinfunction "1_1") (pintype "passive"))
    )
    (net (code "54") (name "Net-(IC7D--IN)") (class "Default")
      (node (ref "C26") (pin "1") (pinfunction "1_1") (pintype "passive"))
      (node (ref "IC7") (pin "13") (pinfunction "-IN_13") (pintype "input"))
      (node (ref "R42") (pin "2") (pinfunction "2_2") (pintype "passive"))
      (node (ref "R43") (pin "1") (pinfunction "1_1") (pintype "passive"))
      (node (ref "R44") (pin "2") (pinfunction "2_2") (pintype "passive"))
      (node (ref "R45") (pin "2") (pinfunction "2_2") (pintype "passive"))
      (node (ref "R46") (pin "2") (pinfunction "2_2") (pintype "passive"))
    )
    (net (code "55") (name "Net-(IC7D-OUT)") (class "Default")
      (node (ref "C26") (pin "2") (pinfunction "2_2") (pintype "passive"))
      (node (ref "IC7") (pin "14") (pinfunction "OUT_14") (pintype "output"))
      (node (ref "R43") (pin "2") (pinfunction "2_2") (pintype "passive"))
      (node (ref "R65") (pin "1") (pinfunction "1_1") (pintype "passive"))
    )
    (net (code "56") (name "Net-(IC8A-+IN)") (class "Default")
      (node (ref "IC8") (pin "3") (pinfunction "+IN_3") (pintype "input"))
      (node (ref "R69") (pin "1") (pinfunction "1_1") (pintype "passive"))
      (node (ref "R70") (pin "2") (pinfunction "2_2") (pintype "passive"))
    )
    (net (code "57") (name "Net-(IC8A--IN)") (class "Default")
      (node (ref "D7") (pin "C") (pinfunction "C_C") (pintype "passive"))
      (node (ref "IC8") (pin "2") (pinfunction "-IN_2") (pintype "input"))
      (node (ref "LED1") (pin "A") (pinfunction "A_A") (pintype "passive"))
      (node (ref "R53") (pin "1") (pinfunction "1_1") (pintype "passive"))
    )
    (net (code "58") (name "Net-(IC8A-OUT)") (class "Default")
      (node (ref "D7") (pin "A") (pinfunction "A_A") (pintype "passive"))
      (node (ref "IC8") (pin "1") (pinfunction "OUT_1") (pintype "output"))
      (node (ref "LED1") (pin "K") (pinfunction "C_K") (pintype "passive"))
    )
    (net (code "59") (name "Net-(IC8B-+IN)") (class "Default")
      (node (ref "IC8") (pin "5") (pinfunction "+IN_5") (pintype "input"))
      (node (ref "R57") (pin "1") (pinfunction "1_1") (pintype "passive"))
      (node (ref "R64") (pin "2") (pinfunction "2_2") (pintype "passive"))
    )
    (net (code "60") (name "Net-(IC8B--IN)") (class "Default")
      (node (ref "D8") (pin "A") (pinfunction "A_A") (pintype "passive"))
      (node (ref "IC8") (pin "6") (pinfunction "-IN_6") (pintype "input"))
      (node (ref "LED2") (pin "K") (pinfunction "C_K") (pintype "passive"))
      (node (ref "R62") (pin "1") (pinfunction "1_1") (pintype "passive"))
    )
    (net (code "61") (name "Net-(IC8B-OUT)") (class "Default")
      (node (ref "D8") (pin "C") (pinfunction "C_C") (pintype "passive"))
      (node (ref "IC8") (pin "7") (pinfunction "OUT_7") (pintype "output"))
      (node (ref "LED2") (pin "A") (pinfunction "A_A") (pintype "passive"))
    )
    (net (code "62") (name "Net-(IC8C--IN)") (class "Default")
      (node (ref "C31") (pin "1") (pinfunction "1_1") (pintype "passive"))
      (node (ref "IC8") (pin "9") (pinfunction "-IN_9") (pintype "input"))
      (node (ref "R56") (pin "2") (pinfunction "2_2") (pintype "passive"))
      (node (ref "R57") (pin "2") (pinfunction "2_2") (pintype "passive"))
      (node (ref "R60") (pin "1") (pinfunction "1_1") (pintype "passive"))
    )
    (net (code "63") (name "Net-(IC8D--IN)") (class "Default")
      (node (ref "D5") (pin "A") (pinfunction "A_A") (pintype "passive"))
      (node (ref "IC8") (pin "13") (pinfunction "-IN_13") (pintype "input"))
      (node (ref "R51") (pin "P$1") (pinfunction "E_P$1") (pintype "passive"))
      (node (ref "R54") (pin "1") (pinfunction "1_1") (pintype "passive"))
    )
    (net (code "64") (name "Net-(IC8D-OUT)") (class "Default")
      (node (ref "D6") (pin "A") (pinfunction "A_A") (pintype "passive"))
      (node (ref "IC8") (pin "14") (pinfunction "OUT_14") (pintype "output"))
      (node (ref "R48") (pin "1") (pinfunction "1_1") (pintype "passive"))
      (node (ref "R68") (pin "2") (pinfunction "2_2") (pintype "passive"))
      (node (ref "R69") (pin "2") (pinfunction "2_2") (pintype "passive"))
    )
    (net (code "65") (name "Net-(J6-2)") (class "Default")
      (node (ref "J6") (pin "P2") (pinfunction "2_P2") (pintype "passive"))
      (node (ref "R63") (pin "1") (pinfunction "1_1") (pintype "passive"))
    )
    (net (code "66") (name "Net-(JP1-Pad1)") (class "Default")
      (node (ref "JP1") (pin "1") (pinfunction "1_1") (pintype "passive"))
      (node (ref "JP1") (pin "2") (pinfunction "2_2") (pintype "passive"))
      (node (ref "P1") (pin "2") (pinfunction "2_2") (pintype "bidirectional"))
    )
    (net (code "67") (name "Net-(L2-Pad2)") (class "Default")
      (node (ref "L2") (pin "2") (pinfunction "2_2") (pintype "passive"))
      (node (ref "P1") (pin "1") (pinfunction "1_1") (pintype "bidirectional"))
    )
    (net (code "68") (name "Net-(Q1-PadE)") (class "Default")
      (node (ref "Q1") (pin "E") (pinfunction "E_E") (pintype "passive"))
      (node (ref "R32") (pin "2") (pinfunction "2_2") (pintype "passive"))
    )
    (net (code "69") (name "Net-(Q2-PadE)") (class "Default")
      (node (ref "Q2") (pin "E") (pinfunction "E_E") (pintype "passive"))
      (node (ref "R30") (pin "2") (pinfunction "2_2") (pintype "passive"))
    )
    (net (code "70") (name "Net-(R16-S)") (class "Default")
      (node (ref "R16") (pin "P$2") (pinfunction "S_P$2") (pintype "passive"))
      (node (ref "R36") (pin "1") (pinfunction "1_1") (pintype "passive"))
    )
    (net (code "71") (name "Net-(R29-S)") (class "Default")
      (node (ref "R29") (pin "P$2") (pinfunction "S_P$2") (pintype "passive"))
      (node (ref "R33") (pin "1") (pinfunction "1_1") (pintype "passive"))
    )
    (net (code "72") (name "Net-(R41-E)") (class "Default")
      (node (ref "R38") (pin "2") (pinfunction "2_2") (pintype "passive"))
      (node (ref "R41") (pin "1") (pinfunction "E_1") (pintype "passive"))
      (node (ref "R41") (pin "2") (pinfunction "S_2") (pintype "passive"))
    )
    (net (code "73") (name "Net-(R51-A)") (class "Default")
      (node (ref "R51") (pin "P$3") (pinfunction "A_P$3") (pintype "passive"))
      (node (ref "R55") (pin "2") (pinfunction "2_2") (pintype "passive"))
    )
    (net (code "74") (name "Net-(R51-S)") (class "Default")
      (node (ref "R51") (pin "P$2") (pinfunction "S_P$2") (pintype "passive"))
      (node (ref "R58") (pin "2") (pinfunction "2_2") (pintype "passive"))
      (node (ref "R61") (pin "2") (pinfunction "2_2") (pintype "passive"))
    )
    (net (code "75") (name "Net-(R52-S)") (class "Default")
      (node (ref "R52") (pin "P$2") (pinfunction "S_P$2") (pintype "passive"))
      (node (ref "R59") (pin "2") (pinfunction "2_2") (pintype "passive"))
    )
    (net (code "76") (name "Net-(R54-Pad2)") (class "Default")
      (node (ref "R54") (pin "2") (pinfunction "2_2") (pintype "passive"))
      (node (ref "R68") (pin "1") (pinfunction "1_1") (pintype "passive"))
    )
    (net (code "77") (name "Net-(SW1A-1)") (class "Default")
      (node (ref "R17") (pin "2") (pinfunction "2_2") (pintype "passive"))
      (node (ref "R18") (pin "2") (pinfunction "2_2") (pintype "passive"))
      (node (ref "SW1") (pin "A1") (pinfunction "1_A1") (pintype "passive"))
    )
    (net (code "78") (name "Net-(SW1A-3)") (class "Default")
      (node (ref "R10") (pin "2") (pinfunction "2_2") (pintype "passive"))
      (node (ref "R12") (pin "2") (pinfunction "2_2") (pintype "passive"))
      (node (ref "R14") (pin "2") (pinfunction "2_2") (pintype "passive"))
      (node (ref "R9") (pin "2") (pinfunction "2_2") (pintype "passive"))
      (node (ref "SW1") (pin "A3") (pinfunction "3_A3") (pintype "passive"))
    )
    (net (code "79") (name "Net-(SW1B-2)") (class "Default")
      (node (ref "C17") (pin "1") (pinfunction "1_1") (pintype "passive"))
      (node (ref "SW1") (pin "B2") (pinfunction "2_B2") (pintype "passive"))
    )
    (net (code "80") (name "REF_+10") (class "Default")
      (node (ref "C18") (pin "1") (pinfunction "1_1") (pintype "passive"))
      (node (ref "IC4") (pin "1") (pinfunction "C_1") (pintype "passive"))
      (node (ref "R21") (pin "2") (pinfunction "2_2") (pintype "passive"))
      (node (ref "R29") (pin "P$1") (pinfunction "E_P$1") (pintype "passive"))
      (node (ref "R63") (pin "2") (pinfunction "2_2") (pintype "passive"))
    )
    (net (code "81") (name "REF_-10") (class "Default")
      (node (ref "C15") (pin "1") (pinfunction "1_1") (pintype "passive"))
      (node (ref "IC3") (pin "2") (pinfunction "A_2") (pintype "passive"))
      (node (ref "R16") (pin "P$3") (pinfunction "A_P$3") (pintype "passive"))
      (node (ref "R19") (pin "2") (pinfunction "2_2") (pintype "passive"))
      (node (ref "R35") (pin "1") (pinfunction "1_1") (pintype "passive"))
    )
    (net (code "82") (name "VCC") (class "Default")
      (node (ref "C12") (pin "1") (pinfunction "1_1") (pintype "passive"))
      (node (ref "C2") (pin "1") (pinfunction "1_1") (pintype "passive"))
      (node (ref "C20") (pin "1") (pinfunction "1_1") (pintype "passive"))
      (node (ref "C23") (pin "1") (pinfunction "1_1") (pintype "passive"))
      (node (ref "C29") (pin "1") (pinfunction "1_1") (pintype "passive"))
      (node (ref "C32") (pin "1") (pinfunction "1_1") (pintype "passive"))
      (node (ref "C6") (pin "+") (pinfunction "+_+") (pintype "passive"))
      (node (ref "IC1") (pin "16") (pinfunction "V+_16") (pintype "power_in"))
      (node (ref "IC2") (pin "4") (pinfunction "V+_4") (pintype "power_in"))
      (node (ref "IC5") (pin "11") (pinfunction "V+_11") (pintype "power_in"))
      (node (ref "IC6") (pin "4") (pinfunction "V+_4") (pintype "power_in"))
      (node (ref "IC7") (pin "4") (pinfunction "V+_4") (pintype "power_in"))
      (node (ref "IC8") (pin "4") (pinfunction "V+_4") (pintype "power_in"))
      (node (ref "L1") (pin "1") (pinfunction "1_1") (pintype "passive"))
      (node (ref "R21") (pin "1") (pinfunction "1_1") (pintype "passive"))
      (node (ref "R70") (pin "1") (pinfunction "1_1") (pintype "passive"))
    )
    (net (code "83") (name "VEE") (class "Default")
      (node (ref "C10") (pin "-") (pinfunction "-_-") (pintype "passive"))
      (node (ref "C11") (pin "2") (pinfunction "2_2") (pintype "passive"))
      (node (ref "C19") (pin "2") (pinfunction "2_2") (pintype "passive"))
      (node (ref "C24") (pin "2") (pinfunction "2_2") (pintype "passive"))
      (node (ref "C28") (pin "2") (pinfunction "2_2") (pintype "passive"))
      (node (ref "C33") (pin "2") (pinfunction "2_2") (pintype "passive"))
      (node (ref "C7") (pin "2") (pinfunction "2_2") (pintype "passive"))
      (node (ref "D2") (pin "A") (pinfunction "A_A") (pintype "passive"))
      (node (ref "IC1") (pin "9") (pinfunction "V-_9") (pintype "power_in"))
      (node (ref "IC2") (pin "11") (pinfunction "V-_11") (pintype "power_in"))
      (node (ref "IC5") (pin "6") (pinfunction "V-_6") (pintype "power_in"))
      (node (ref "IC6") (pin "11") (pinfunction "V-_11") (pintype "power_in"))
      (node (ref "IC7") (pin "11") (pinfunction "V-_11") (pintype "power_in"))
      (node (ref "IC8") (pin "11") (pinfunction "V-_11") (pintype "power_in"))
      (node (ref "L2") (pin "1") (pinfunction "1_1") (pintype "passive"))
      (node (ref "R19") (pin "1") (pinfunction "1_1") (pintype "passive"))
    )
    (net (code "84") (name "unconnected-(IC1E-MODE-Pad1)") (class "Default")
      (node (ref "IC1") (pin "1") (pinfunction "MODE_1") (pintype "input"))
    )
    (net (code "85") (name "unconnected-(IC5A-B-Pad7)") (class "Default")
      (node (ref "IC5") (pin "7") (pinfunction "B_7") (pintype "passive"))
    )
    (net (code "86") (name "unconnected-(IC5A-E-Pad8)") (class "Default")
      (node (ref "IC5") (pin "8") (pinfunction "E_8") (pintype "passive"))
    )
    (net (code "87") (name "unconnected-(IC5B-B-Pad10)") (class "Default")
      (node (ref "IC5") (pin "10") (pinfunction "B_10") (pintype "passive"))
    )
    (net (code "88") (name "unconnected-(IC5B-E-Pad9)") (class "Default")
      (node (ref "IC5") (pin "9") (pinfunction "E_9") (pintype "passive"))
    )
    (net (code "89") (name "unconnected-(IC5C-I_DIODE-Pad2)") (class "Default")
      (node (ref "IC5") (pin "2") (pinfunction "I_DIODE_2") (pintype "input"))
    )
    (net (code "90") (name "unconnected-(IC5D-I_DIODE-Pad15)") (class "Default")
      (node (ref "IC5") (pin "15") (pinfunction "I_DIODE_15") (pintype "input"))
    )
    (net (code "91") (name "unconnected-(J7-2-PadP2)") (class "Default")
      (node (ref "J7") (pin "P2") (pinfunction "2_P2") (pintype "passive"))
    )
    (net (code "92") (name "unconnected-(J8-2-PadP2)") (class "Default")
      (node (ref "J8") (pin "P2") (pinfunction "2_P2") (pintype "passive"))
    )
    (net (code "93") (name "unconnected-(J9-2-PadP2)") (class "Default")
      (node (ref "J9") (pin "P2") (pinfunction "2_P2") (pintype "passive"))
    )
  )
)
